# DriverBoard.net
KiCad netlist of a schematic drawn in Altium Designer
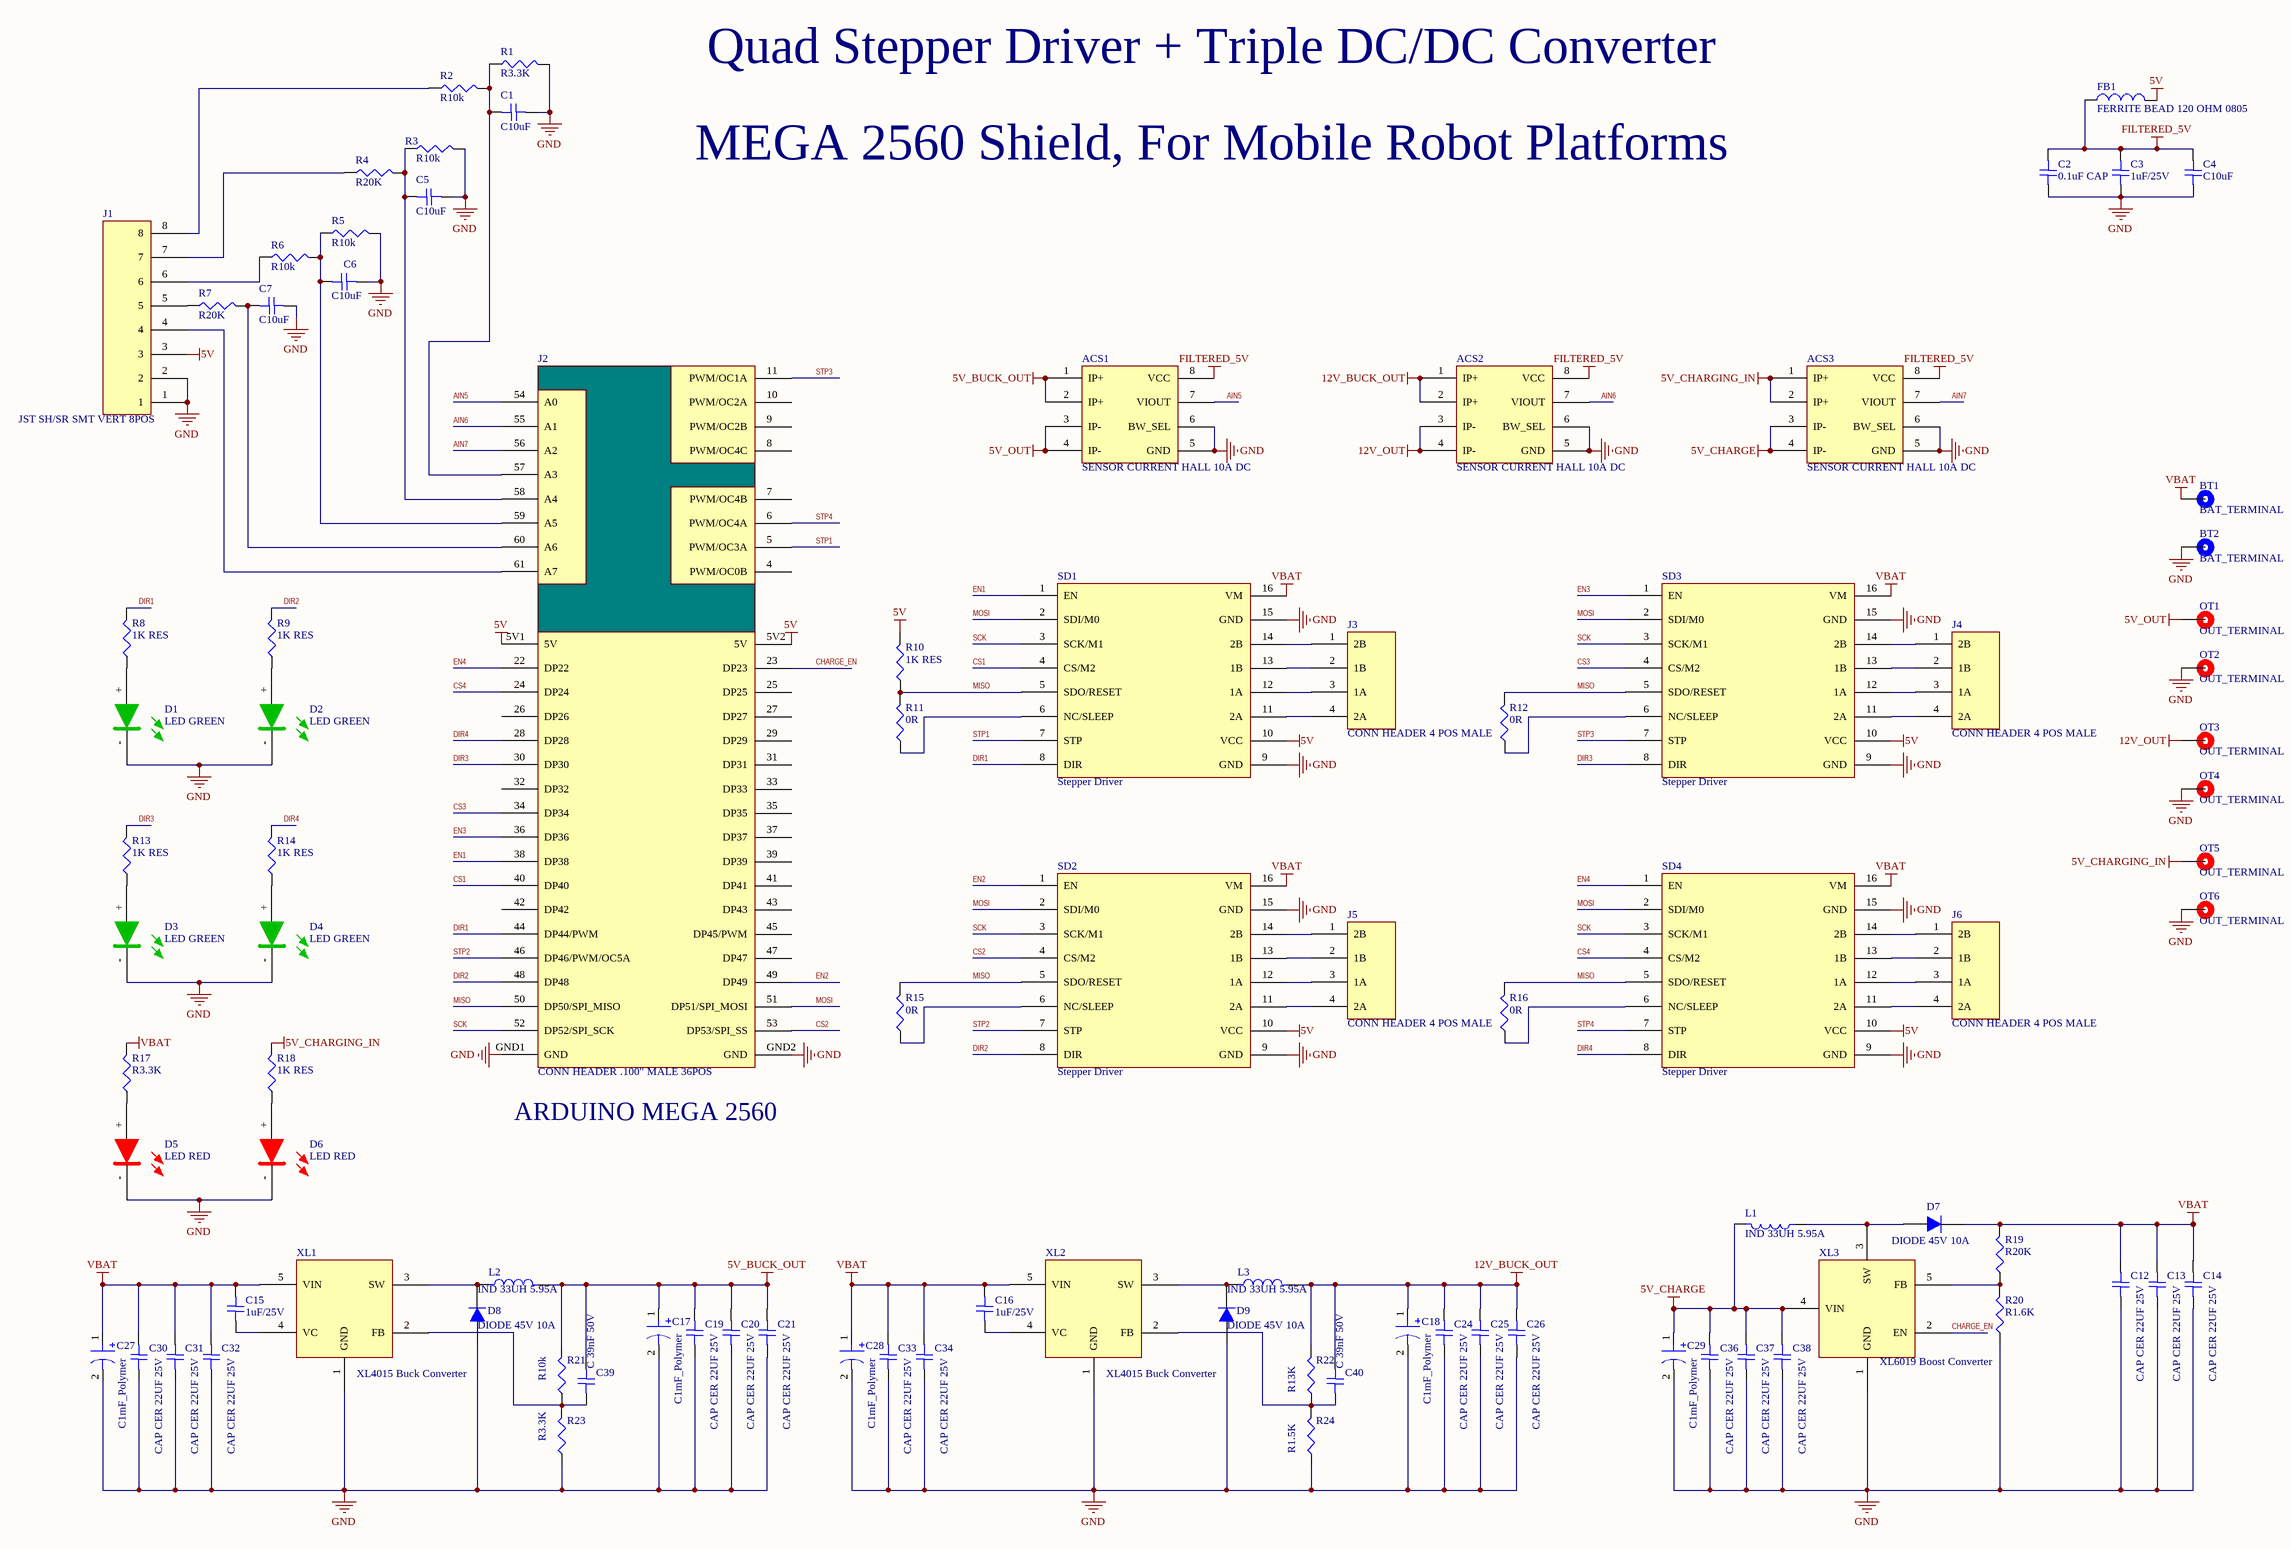
[diagram p0: DriverBoard.SchDoc]

(export (version "E")
  (design (tool "Eeschema 10.0.6"))
  (components
    (comp (ref "ACS1")
      (value "SENSOR CURRENT HALL 10A DC")
      (footprint "SOIC_8")
      (fields
        (field (name "MANUFACTURER") "Allegro MicroSystems")
        (field (name "MANUFACTURER PART NUMBER") "ACS723LLCTR-10AU-T")
      )
      (libsource (lib "DriverBoard") (part "ACS723LLCTR-10AU-T"))
    )
    (comp (ref "ACS2")
      (value "SENSOR CURRENT HALL 10A DC")
      (footprint "SOIC_8")
      (fields
        (field (name "MANUFACTURER") "Allegro MicroSystems")
        (field (name "MANUFACTURER PART NUMBER") "ACS723LLCTR-10AU-T")
      )
      (libsource (lib "DriverBoard") (part "ACS723LLCTR-10AU-T"))
    )
    (comp (ref "ACS3")
      (value "SENSOR CURRENT HALL 10A DC")
      (footprint "SOIC_8")
      (fields
        (field (name "MANUFACTURER") "Allegro MicroSystems")
        (field (name "MANUFACTURER PART NUMBER") "ACS723LLCTR-10AU-T")
      )
      (libsource (lib "DriverBoard") (part "ACS723LLCTR-10AU-T"))
    )
    (comp (ref "BT1")
      (value "BAT_TERMINAL")
      (footprint "BATTERY_TERMINALS")
      (libsource (lib "DriverBoard") (part "BAT_TERMINAL"))
    )
    (comp (ref "BT2")
      (value "BAT_TERMINAL")
      (footprint "BATTERY_TERMINALS")
      (libsource (lib "DriverBoard") (part "BAT_TERMINAL"))
    )
    (comp (ref "C1")
      (value "C10uF")
      (footprint "C0805")
      (description "Cap Ceramic 10uF 10V X5R 10% SMD 0805 85C Embossed T/R")
      (fields
        (field (name "MANUFACTURER") "Samsung")
        (field (name "MANUFACTURER PART NUMBER") "CL21A106KPFNNNG")
      )
      (libsource (lib "DriverBoard") (part "CL21A106KPFNNNG"))
    )
    (comp (ref "C2")
      (value "0.1uF CAP")
      (footprint "C0805")
      (description "Cap Ceramic 0.1uF 50V Y5V -20% to 80% SMD 0805 85C Paper T/R")
      (fields
        (field (name "MANUFACTURER") "Samsung")
        (field (name "MANUFACTURER PART NUMBER") "CL21F104ZBCNNNC")
      )
      (libsource (lib "DriverBoard") (part "CL21F104ZBCNNNC"))
    )
    (comp (ref "C3")
      (value "1uF/25V")
      (footprint "C0805")
      (description "CAP CER 1UF 25V X5R 0805")
      (fields
        (field (name "MANUFACTURER") "TDK Corporation")
        (field (name "MANUFACTURER PART NUMBER") "C2012X5R1E105K125AA")
      )
      (libsource (lib "DriverBoard") (part "C2012X5R1E105K125AA"))
    )
    (comp (ref "C4")
      (value "C10uF")
      (footprint "C0805")
      (description "Cap Ceramic 10uF 10V X5R 10% SMD 0805 85C Embossed T/R")
      (fields
        (field (name "MANUFACTURER") "Samsung")
        (field (name "MANUFACTURER PART NUMBER") "CL21A106KPFNNNG")
      )
      (libsource (lib "DriverBoard") (part "CL21A106KPFNNNG"))
    )
    (comp (ref "C5")
      (value "C10uF")
      (footprint "C0805")
      (description "Cap Ceramic 10uF 10V X5R 10% SMD 0805 85C Embossed T/R")
      (fields
        (field (name "MANUFACTURER") "Samsung")
        (field (name "MANUFACTURER PART NUMBER") "CL21A106KPFNNNG")
      )
      (libsource (lib "DriverBoard") (part "CL21A106KPFNNNG"))
    )
    (comp (ref "C6")
      (value "C10uF")
      (footprint "C0805")
      (description "Cap Ceramic 10uF 10V X5R 10% SMD 0805 85C Embossed T/R")
      (fields
        (field (name "MANUFACTURER") "Samsung")
        (field (name "MANUFACTURER PART NUMBER") "CL21A106KPFNNNG")
      )
      (libsource (lib "DriverBoard") (part "CL21A106KPFNNNG"))
    )
    (comp (ref "C7")
      (value "C10uF")
      (footprint "C0805")
      (description "Cap Ceramic 10uF 10V X5R 10% SMD 0805 85C Embossed T/R")
      (fields
        (field (name "MANUFACTURER") "Samsung")
        (field (name "MANUFACTURER PART NUMBER") "CL21A106KPFNNNG")
      )
      (libsource (lib "DriverBoard") (part "CL21A106KPFNNNG"))
    )
    (comp (ref "C12")
      (value "CAP CER 22UF 25V")
      (footprint "C1210")
      (description "CAP CER 22UF 25V X5R 1210")
      (fields
        (field (name "MANUFACTURER") "Samsung")
        (field (name "MANUFACTURER PART NUMBER") "CL32A226MAJNNNE")
      )
      (libsource (lib "DriverBoard") (part "CL32A226MAJNNNE"))
    )
    (comp (ref "C13")
      (value "CAP CER 22UF 25V")
      (footprint "C1210")
      (description "CAP CER 22UF 25V X5R 1210")
      (fields
        (field (name "MANUFACTURER") "Samsung")
        (field (name "MANUFACTURER PART NUMBER") "CL32A226MAJNNNE")
      )
      (libsource (lib "DriverBoard") (part "CL32A226MAJNNNE"))
    )
    (comp (ref "C14")
      (value "CAP CER 22UF 25V")
      (footprint "C1210")
      (description "CAP CER 22UF 25V X5R 1210")
      (fields
        (field (name "MANUFACTURER") "Samsung")
        (field (name "MANUFACTURER PART NUMBER") "CL32A226MAJNNNE")
      )
      (libsource (lib "DriverBoard") (part "CL32A226MAJNNNE"))
    )
    (comp (ref "C15")
      (value "1uF/25V")
      (footprint "C0805")
      (description "CAP CER 1UF 25V X5R 0805")
      (fields
        (field (name "MANUFACTURER") "TDK Corporation")
        (field (name "MANUFACTURER PART NUMBER") "C2012X5R1E105K125AA")
      )
      (libsource (lib "DriverBoard") (part "C2012X5R1E105K125AA"))
    )
    (comp (ref "C16")
      (value "1uF/25V")
      (footprint "C0805")
      (description "CAP CER 1UF 25V X5R 0805")
      (fields
        (field (name "MANUFACTURER") "TDK Corporation")
        (field (name "MANUFACTURER PART NUMBER") "C2012X5R1E105K125AA")
      )
      (libsource (lib "DriverBoard") (part "C2012X5R1E105K125AA"))
    )
    (comp (ref "C17")
      (value "C1mF_Polymer")
      (footprint "POLY_CAP_10X21")
      (description "Cap Aluminum Polymer 680uF 20VDC 20% (10 X 11.5mm) Radial 5mm 0.012 Ohm 5400mA 2000h 105C Bulk")
      (fields
        (field (name "MANUFACTURER") "United Chemi-Con")
        (field (name "MANUFACTURER PART NUMBER") "APSG200ELL681MJB5S")
      )
      (libsource (lib "DriverBoard") (part "APSG200ELL681MJB5S"))
    )
    (comp (ref "C18")
      (value "C1mF_Polymer")
      (footprint "POLY_CAP_10X21")
      (description "Cap Aluminum Polymer 680uF 20VDC 20% (10 X 11.5mm) Radial 5mm 0.012 Ohm 5400mA 2000h 105C Bulk")
      (fields
        (field (name "MANUFACTURER") "United Chemi-Con")
        (field (name "MANUFACTURER PART NUMBER") "APSG200ELL681MJB5S")
      )
      (libsource (lib "DriverBoard") (part "APSG200ELL681MJB5S"))
    )
    (comp (ref "C19")
      (value "CAP CER 22UF 25V")
      (footprint "C1210")
      (description "CAP CER 22UF 25V X5R 1210")
      (fields
        (field (name "MANUFACTURER") "Samsung")
        (field (name "MANUFACTURER PART NUMBER") "CL32A226MAJNNNE")
      )
      (libsource (lib "DriverBoard") (part "CL32A226MAJNNNE"))
    )
    (comp (ref "C20")
      (value "CAP CER 22UF 25V")
      (footprint "C1210")
      (description "CAP CER 22UF 25V X5R 1210")
      (fields
        (field (name "MANUFACTURER") "Samsung")
        (field (name "MANUFACTURER PART NUMBER") "CL32A226MAJNNNE")
      )
      (libsource (lib "DriverBoard") (part "CL32A226MAJNNNE"))
    )
    (comp (ref "C21")
      (value "CAP CER 22UF 25V")
      (footprint "C1210")
      (description "CAP CER 22UF 25V X5R 1210")
      (fields
        (field (name "MANUFACTURER") "Samsung")
        (field (name "MANUFACTURER PART NUMBER") "CL32A226MAJNNNE")
      )
      (libsource (lib "DriverBoard") (part "CL32A226MAJNNNE"))
    )
    (comp (ref "C24")
      (value "CAP CER 22UF 25V")
      (footprint "C1210")
      (description "CAP CER 22UF 25V X5R 1210")
      (fields
        (field (name "MANUFACTURER") "Samsung")
        (field (name "MANUFACTURER PART NUMBER") "CL32A226MAJNNNE")
      )
      (libsource (lib "DriverBoard") (part "CL32A226MAJNNNE"))
    )
    (comp (ref "C25")
      (value "CAP CER 22UF 25V")
      (footprint "C1210")
      (description "CAP CER 22UF 25V X5R 1210")
      (fields
        (field (name "MANUFACTURER") "Samsung")
        (field (name "MANUFACTURER PART NUMBER") "CL32A226MAJNNNE")
      )
      (libsource (lib "DriverBoard") (part "CL32A226MAJNNNE"))
    )
    (comp (ref "C26")
      (value "CAP CER 22UF 25V")
      (footprint "C1210")
      (description "CAP CER 22UF 25V X5R 1210")
      (fields
        (field (name "MANUFACTURER") "Samsung")
        (field (name "MANUFACTURER PART NUMBER") "CL32A226MAJNNNE")
      )
      (libsource (lib "DriverBoard") (part "CL32A226MAJNNNE"))
    )
    (comp (ref "C27")
      (value "C1mF_Polymer")
      (footprint "POLY_CAP_10X21")
      (description "Cap Aluminum Polymer 680uF 20VDC 20% (10 X 11.5mm) Radial 5mm 0.012 Ohm 5400mA 2000h 105C Bulk")
      (fields
        (field (name "MANUFACTURER") "United Chemi-Con")
        (field (name "MANUFACTURER PART NUMBER") "APSG200ELL681MJB5S")
      )
      (libsource (lib "DriverBoard") (part "APSG200ELL681MJB5S"))
    )
    (comp (ref "C28")
      (value "C1mF_Polymer")
      (footprint "POLY_CAP_10X21")
      (description "Cap Aluminum Polymer 680uF 20VDC 20% (10 X 11.5mm) Radial 5mm 0.012 Ohm 5400mA 2000h 105C Bulk")
      (fields
        (field (name "MANUFACTURER") "United Chemi-Con")
        (field (name "MANUFACTURER PART NUMBER") "APSG200ELL681MJB5S")
      )
      (libsource (lib "DriverBoard") (part "APSG200ELL681MJB5S"))
    )
    (comp (ref "C29")
      (value "C1mF_Polymer")
      (footprint "POLY_CAP_10X21")
      (description "Cap Aluminum Polymer 680uF 20VDC 20% (10 X 11.5mm) Radial 5mm 0.012 Ohm 5400mA 2000h 105C Bulk")
      (fields
        (field (name "MANUFACTURER") "United Chemi-Con")
        (field (name "MANUFACTURER PART NUMBER") "APSG200ELL681MJB5S")
      )
      (libsource (lib "DriverBoard") (part "APSG200ELL681MJB5S"))
    )
    (comp (ref "C30")
      (value "CAP CER 22UF 25V")
      (footprint "C1210")
      (description "CAP CER 22UF 25V X5R 1210")
      (fields
        (field (name "MANUFACTURER") "Samsung")
        (field (name "MANUFACTURER PART NUMBER") "CL32A226MAJNNNE")
      )
      (libsource (lib "DriverBoard") (part "CL32A226MAJNNNE"))
    )
    (comp (ref "C31")
      (value "CAP CER 22UF 25V")
      (footprint "C1210")
      (description "CAP CER 22UF 25V X5R 1210")
      (fields
        (field (name "MANUFACTURER") "Samsung")
        (field (name "MANUFACTURER PART NUMBER") "CL32A226MAJNNNE")
      )
      (libsource (lib "DriverBoard") (part "CL32A226MAJNNNE"))
    )
    (comp (ref "C32")
      (value "CAP CER 22UF 25V")
      (footprint "C1210")
      (description "CAP CER 22UF 25V X5R 1210")
      (fields
        (field (name "MANUFACTURER") "Samsung")
        (field (name "MANUFACTURER PART NUMBER") "CL32A226MAJNNNE")
      )
      (libsource (lib "DriverBoard") (part "CL32A226MAJNNNE"))
    )
    (comp (ref "C33")
      (value "CAP CER 22UF 25V")
      (footprint "C1210")
      (description "CAP CER 22UF 25V X5R 1210")
      (fields
        (field (name "MANUFACTURER") "Samsung")
        (field (name "MANUFACTURER PART NUMBER") "CL32A226MAJNNNE")
      )
      (libsource (lib "DriverBoard") (part "CL32A226MAJNNNE"))
    )
    (comp (ref "C34")
      (value "CAP CER 22UF 25V")
      (footprint "C1210")
      (description "CAP CER 22UF 25V X5R 1210")
      (fields
        (field (name "MANUFACTURER") "Samsung")
        (field (name "MANUFACTURER PART NUMBER") "CL32A226MAJNNNE")
      )
      (libsource (lib "DriverBoard") (part "CL32A226MAJNNNE"))
    )
    (comp (ref "C36")
      (value "CAP CER 22UF 25V")
      (footprint "C1210")
      (description "CAP CER 22UF 25V X5R 1210")
      (fields
        (field (name "MANUFACTURER") "Samsung")
        (field (name "MANUFACTURER PART NUMBER") "CL32A226MAJNNNE")
      )
      (libsource (lib "DriverBoard") (part "CL32A226MAJNNNE"))
    )
    (comp (ref "C37")
      (value "CAP CER 22UF 25V")
      (footprint "C1210")
      (description "CAP CER 22UF 25V X5R 1210")
      (fields
        (field (name "MANUFACTURER") "Samsung")
        (field (name "MANUFACTURER PART NUMBER") "CL32A226MAJNNNE")
      )
      (libsource (lib "DriverBoard") (part "CL32A226MAJNNNE"))
    )
    (comp (ref "C38")
      (value "CAP CER 22UF 25V")
      (footprint "C1210")
      (description "CAP CER 22UF 25V X5R 1210")
      (fields
        (field (name "MANUFACTURER") "Samsung")
        (field (name "MANUFACTURER PART NUMBER") "CL32A226MAJNNNE")
      )
      (libsource (lib "DriverBoard") (part "CL32A226MAJNNNE"))
    )
    (comp (ref "C39")
      (value "C 39nF 50V")
      (footprint "C0805")
      (description "Multilayer Ceramic Capacitors 50volts 39000pF X7R 10%")
      (fields
        (field (name "MANUFACTURER") "KEMET")
        (field (name "MANUFACTURER PART NUMBER") "C0805C393K5RACTU")
      )
      (libsource (lib "DriverBoard") (part "C0805C393K5RACTU"))
    )
    (comp (ref "C40")
      (value "C 39nF 50V")
      (footprint "C0805")
      (description "Multilayer Ceramic Capacitors 50volts 39000pF X7R 10%")
      (fields
        (field (name "MANUFACTURER") "KEMET")
        (field (name "MANUFACTURER PART NUMBER") "C0805C393K5RACTU")
      )
      (libsource (lib "DriverBoard") (part "C0805C393K5RACTU"))
    )
    (comp (ref "D1")
      (value "LED GREEN")
      (footprint "LED_0805")
      (description "LED GREEN CLEAR CHIP SMD")
      (fields
        (field (name "MANUFACTURER") "Vishay Lite-On")
        (field (name "MANUFACTURER PART NUMBER") "LTST-C171GKT")
      )
      (libsource (lib "DriverBoard") (part "LTST-C171GKT"))
    )
    (comp (ref "D2")
      (value "LED GREEN")
      (footprint "LED_0805")
      (description "LED GREEN CLEAR CHIP SMD")
      (fields
        (field (name "MANUFACTURER") "Vishay Lite-On")
        (field (name "MANUFACTURER PART NUMBER") "LTST-C171GKT")
      )
      (libsource (lib "DriverBoard") (part "LTST-C171GKT"))
    )
    (comp (ref "D3")
      (value "LED GREEN")
      (footprint "LED_0805")
      (description "LED GREEN CLEAR CHIP SMD")
      (fields
        (field (name "MANUFACTURER") "Vishay Lite-On")
        (field (name "MANUFACTURER PART NUMBER") "LTST-C171GKT")
      )
      (libsource (lib "DriverBoard") (part "LTST-C171GKT"))
    )
    (comp (ref "D4")
      (value "LED GREEN")
      (footprint "LED_0805")
      (description "LED GREEN CLEAR CHIP SMD")
      (fields
        (field (name "MANUFACTURER") "Vishay Lite-On")
        (field (name "MANUFACTURER PART NUMBER") "LTST-C171GKT")
      )
      (libsource (lib "DriverBoard") (part "LTST-C171GKT"))
    )
    (comp (ref "D5")
      (value "LED RED")
      (footprint "LED_0805")
      (description "LED RED CLEAR SMD")
      (fields
        (field (name "MANUFACTURER") "Vishay Lite-On")
        (field (name "MANUFACTURER PART NUMBER") "LTST-C171KRKT")
      )
      (libsource (lib "DriverBoard") (part "LTST-C171KRKT"))
    )
    (comp (ref "D6")
      (value "LED RED")
      (footprint "LED_0805")
      (description "LED RED CLEAR SMD")
      (fields
        (field (name "MANUFACTURER") "Vishay Lite-On")
        (field (name "MANUFACTURER PART NUMBER") "LTST-C171KRKT")
      )
      (libsource (lib "DriverBoard") (part "LTST-C171KRKT"))
    )
    (comp (ref "D7")
      (value "DIODE 45V 10A")
      (footprint "TO252_3")
      (description "DIODE SCHOTTKY 45V 10A DPAK")
      (fields
        (field (name "MANUFACTURER") "ON Semiconductor")
        (field (name "MANUFACTURER PART NUMBER") "MBRD1045T4G")
      )
      (libsource (lib "DriverBoard") (part "MBRD1045T4G"))
    )
    (comp (ref "D8")
      (value "DIODE 45V 10A")
      (footprint "TO252_3")
      (description "DIODE SCHOTTKY 45V 10A DPAK")
      (fields
        (field (name "MANUFACTURER") "ON Semiconductor")
        (field (name "MANUFACTURER PART NUMBER") "MBRD1045T4G")
      )
      (libsource (lib "DriverBoard") (part "MBRD1045T4G"))
    )
    (comp (ref "D9")
      (value "DIODE 45V 10A")
      (footprint "TO252_3")
      (description "DIODE SCHOTTKY 45V 10A DPAK")
      (fields
        (field (name "MANUFACTURER") "ON Semiconductor")
        (field (name "MANUFACTURER PART NUMBER") "MBRD1045T4G")
      )
      (libsource (lib "DriverBoard") (part "MBRD1045T4G"))
    )
    (comp (ref "FB1")
      (value "FERRITE BEAD 120 OHM 0805")
      (footprint "FB_0805")
      (description "FERRITE BEAD 120 OHM 0805 1LN")
      (fields
        (field (name "MANUFACTURER") "Wurth Electronics")
        (field (name "MANUFACTURER PART NUMBER") "742792023")
      )
      (libsource (lib "DriverBoard") (part "742792023"))
    )
    (comp (ref "J1")
      (value "JST SH/SR SMT VERT 8POS")
      (footprint "JST_SH_8")
      (description "CONN RCPT SR 8 POS 1.0MM TIN")
      (fields (field (name "MANUFACTURER") "JST") (field (name "MANUFACTURER PART NUMBER") "08SR-3S"))
      (libsource (lib "DriverBoard") (part "08SR-3S"))
    )
    (comp (ref "J2")
      (value "CONN HEADER .100\" MALE 36POS")
      (footprint "DIP36_MALE")
      (description "CONN HEADER .100\" DUAL STR 36POS")
      (fields
        (field (name "MANUFACTURER") "Sullins")
        (field (name "MANUFACTURER PART NUMBER") "PREC018DAAN-RC")
      )
      (libsource (lib "DriverBoard") (part "PREC018DAAN-RC"))
    )
    (comp (ref "J3")
      (value "CONN HEADER 4 POS MALE")
      (footprint "DIP4")
      (description "CONN HEADER VERT 4POS 2.54MM")
      (fields
        (field (name "MANUFACTURER") "Sullins")
        (field (name "MANUFACTURER PART NUMBER") "PREC004SAAN-RC")
      )
      (libsource (lib "DriverBoard") (part "PREC004SAAN-RC"))
    )
    (comp (ref "J4")
      (value "CONN HEADER 4 POS MALE")
      (footprint "DIP4")
      (description "CONN HEADER VERT 4POS 2.54MM")
      (fields
        (field (name "MANUFACTURER") "Sullins")
        (field (name "MANUFACTURER PART NUMBER") "PREC004SAAN-RC")
      )
      (libsource (lib "DriverBoard") (part "PREC004SAAN-RC"))
    )
    (comp (ref "J5")
      (value "CONN HEADER 4 POS MALE")
      (footprint "DIP4")
      (description "CONN HEADER VERT 4POS 2.54MM")
      (fields
        (field (name "MANUFACTURER") "Sullins")
        (field (name "MANUFACTURER PART NUMBER") "PREC004SAAN-RC")
      )
      (libsource (lib "DriverBoard") (part "PREC004SAAN-RC"))
    )
    (comp (ref "J6")
      (value "CONN HEADER 4 POS MALE")
      (footprint "DIP4")
      (description "CONN HEADER VERT 4POS 2.54MM")
      (fields
        (field (name "MANUFACTURER") "Sullins")
        (field (name "MANUFACTURER PART NUMBER") "PREC004SAAN-RC")
      )
      (libsource (lib "DriverBoard") (part "PREC004SAAN-RC"))
    )
    (comp (ref "L1")
      (value "IND 33UH 5.95A")
      (footprint "13X13X9IND")
      (description "COILCRAFT   SER1390-333MLD   INDUCTOR, 33UH, 5.95A, 20%, 15.7MHZ,REEL")
      (fields
        (field (name "MANUFACTURER") "Coilcraft")
        (field (name "MANUFACTURER PART NUMBER") "SER1390-333MLD")
      )
      (libsource (lib "DriverBoard") (part "SER1390-333MLD"))
    )
    (comp (ref "L2")
      (value "IND 33UH 5.95A")
      (footprint "13X13X9IND")
      (description "COILCRAFT   SER1390-333MLD   INDUCTOR, 33UH, 5.95A, 20%, 15.7MHZ,REEL")
      (fields
        (field (name "MANUFACTURER") "Coilcraft")
        (field (name "MANUFACTURER PART NUMBER") "SER1390-333MLD")
      )
      (libsource (lib "DriverBoard") (part "SER1390-333MLD"))
    )
    (comp (ref "L3")
      (value "IND 33UH 5.95A")
      (footprint "13X13X9IND")
      (description "COILCRAFT   SER1390-333MLD   INDUCTOR, 33UH, 5.95A, 20%, 15.7MHZ,REEL")
      (fields
        (field (name "MANUFACTURER") "Coilcraft")
        (field (name "MANUFACTURER PART NUMBER") "SER1390-333MLD")
      )
      (libsource (lib "DriverBoard") (part "SER1390-333MLD"))
    )
    (comp (ref "OT1")
      (value "OUT_TERMINAL")
      (footprint "OUTPUT_TERMINALS")
      (libsource (lib "DriverBoard") (part "OUT_TERMINAL"))
    )
    (comp (ref "OT2")
      (value "OUT_TERMINAL")
      (footprint "OUTPUT_TERMINALS")
      (libsource (lib "DriverBoard") (part "OUT_TERMINAL"))
    )
    (comp (ref "OT3")
      (value "OUT_TERMINAL")
      (footprint "OUTPUT_TERMINALS")
      (libsource (lib "DriverBoard") (part "OUT_TERMINAL"))
    )
    (comp (ref "OT4")
      (value "OUT_TERMINAL")
      (footprint "OUTPUT_TERMINALS")
      (libsource (lib "DriverBoard") (part "OUT_TERMINAL"))
    )
    (comp (ref "OT5")
      (value "OUT_TERMINAL")
      (footprint "OUTPUT_TERMINALS")
      (libsource (lib "DriverBoard") (part "OUT_TERMINAL"))
    )
    (comp (ref "OT6")
      (value "OUT_TERMINAL")
      (footprint "OUTPUT_TERMINALS")
      (libsource (lib "DriverBoard") (part "OUT_TERMINAL"))
    )
    (comp (ref "R1")
      (value "R3.3K")
      (footprint "R0805")
      (description "RES SMD 3.3K OHM 1% 1/8W 0805")
      (fields
        (field (name "MANUFACTURER") "Yageo")
        (field (name "MANUFACTURER PART NUMBER") "RC0805FR-073K3L")
      )
      (libsource (lib "DriverBoard") (part "RC0805FR-073K3L"))
    )
    (comp (ref "R2")
      (value "R10k")
      (footprint "R0805")
      (description "RES SMD 10K OHM 1% 1/8W 0805")
      (fields
        (field (name "MANUFACTURER") "Yageo")
        (field (name "MANUFACTURER PART NUMBER") "RC0805FR-0710KL")
      )
      (libsource (lib "DriverBoard") (part "RC0805FR-0710KL"))
    )
    (comp (ref "R3")
      (value "R10k")
      (footprint "R0805")
      (description "RES SMD 10K OHM 1% 1/8W 0805")
      (fields
        (field (name "MANUFACTURER") "Yageo")
        (field (name "MANUFACTURER PART NUMBER") "RC0805FR-0710KL")
      )
      (libsource (lib "DriverBoard") (part "RC0805FR-0710KL"))
    )
    (comp (ref "R4")
      (value "R20K")
      (footprint "R0805")
      (description "RES SMD 20K OHM 0.1% 1/8W 0805")
      (fields
        (field (name "MANUFACTURER") "Yageo")
        (field (name "MANUFACTURER PART NUMBER") "RT0805BRC0720KL")
      )
      (libsource (lib "DriverBoard") (part "RT0805BRC0720KL"))
    )
    (comp (ref "R5")
      (value "R10k")
      (footprint "R0805")
      (description "RES SMD 10K OHM 1% 1/8W 0805")
      (fields
        (field (name "MANUFACTURER") "Yageo")
        (field (name "MANUFACTURER PART NUMBER") "RC0805FR-0710KL")
      )
      (libsource (lib "DriverBoard") (part "RC0805FR-0710KL"))
    )
    (comp (ref "R6")
      (value "R10k")
      (footprint "R0805")
      (description "RES SMD 10K OHM 1% 1/8W 0805")
      (fields
        (field (name "MANUFACTURER") "Yageo")
        (field (name "MANUFACTURER PART NUMBER") "RC0805FR-0710KL")
      )
      (libsource (lib "DriverBoard") (part "RC0805FR-0710KL"))
    )
    (comp (ref "R7")
      (value "R20K")
      (footprint "R0805")
      (description "RES SMD 20K OHM 0.1% 1/8W 0805")
      (fields
        (field (name "MANUFACTURER") "Yageo")
        (field (name "MANUFACTURER PART NUMBER") "RT0805BRC0720KL")
      )
      (libsource (lib "DriverBoard") (part "RT0805BRC0720KL"))
    )
    (comp (ref "R8")
      (value "1K RES")
      (footprint "R0805")
      (description "RES 1K OHM 1% 1/4W 0805")
      (fields
        (field (name "MANUFACTURER") "Stackpole Electronics")
        (field (name "MANUFACTURER PART NUMBER") "RNCP0805FTD1K00")
      )
      (libsource (lib "DriverBoard") (part "RNCP0805FTD1K00"))
    )
    (comp (ref "R9")
      (value "1K RES")
      (footprint "R0805")
      (description "RES 1K OHM 1% 1/4W 0805")
      (fields
        (field (name "MANUFACTURER") "Stackpole Electronics")
        (field (name "MANUFACTURER PART NUMBER") "RNCP0805FTD1K00")
      )
      (libsource (lib "DriverBoard") (part "RNCP0805FTD1K00"))
    )
    (comp (ref "R10")
      (value "1K RES")
      (footprint "R0805")
      (description "RES 1K OHM 1% 1/4W 0805")
      (fields
        (field (name "MANUFACTURER") "Stackpole Electronics")
        (field (name "MANUFACTURER PART NUMBER") "RNCP0805FTD1K00")
      )
      (libsource (lib "DriverBoard") (part "RNCP0805FTD1K00"))
    )
    (comp (ref "R11")
      (value "0R")
      (footprint "R0805")
      (description "RES SMD 0 OHM JUMPER 1/8W 0805")
      (fields
        (field (name "MANUFACTURER") "Yageo")
        (field (name "MANUFACTURER PART NUMBER") "RC0805JR-070RL")
      )
      (libsource (lib "DriverBoard") (part "RC0805JR-070RL"))
    )
    (comp (ref "R12")
      (value "0R")
      (footprint "R0805")
      (description "RES SMD 0 OHM JUMPER 1/8W 0805")
      (fields
        (field (name "MANUFACTURER") "Yageo")
        (field (name "MANUFACTURER PART NUMBER") "RC0805JR-070RL")
      )
      (libsource (lib "DriverBoard") (part "RC0805JR-070RL"))
    )
    (comp (ref "R13")
      (value "1K RES")
      (footprint "R0805")
      (description "RES 1K OHM 1% 1/4W 0805")
      (fields
        (field (name "MANUFACTURER") "Stackpole Electronics")
        (field (name "MANUFACTURER PART NUMBER") "RNCP0805FTD1K00")
      )
      (libsource (lib "DriverBoard") (part "RNCP0805FTD1K00"))
    )
    (comp (ref "R14")
      (value "1K RES")
      (footprint "R0805")
      (description "RES 1K OHM 1% 1/4W 0805")
      (fields
        (field (name "MANUFACTURER") "Stackpole Electronics")
        (field (name "MANUFACTURER PART NUMBER") "RNCP0805FTD1K00")
      )
      (libsource (lib "DriverBoard") (part "RNCP0805FTD1K00"))
    )
    (comp (ref "R15")
      (value "0R")
      (footprint "R0805")
      (description "RES SMD 0 OHM JUMPER 1/8W 0805")
      (fields
        (field (name "MANUFACTURER") "Yageo")
        (field (name "MANUFACTURER PART NUMBER") "RC0805JR-070RL")
      )
      (libsource (lib "DriverBoard") (part "RC0805JR-070RL"))
    )
    (comp (ref "R16")
      (value "0R")
      (footprint "R0805")
      (description "RES SMD 0 OHM JUMPER 1/8W 0805")
      (fields
        (field (name "MANUFACTURER") "Yageo")
        (field (name "MANUFACTURER PART NUMBER") "RC0805JR-070RL")
      )
      (libsource (lib "DriverBoard") (part "RC0805JR-070RL"))
    )
    (comp (ref "R17")
      (value "R3.3K")
      (footprint "R0805")
      (description "RES SMD 3.3K OHM 1% 1/8W 0805")
      (fields
        (field (name "MANUFACTURER") "Yageo")
        (field (name "MANUFACTURER PART NUMBER") "RC0805FR-073K3L")
      )
      (libsource (lib "DriverBoard") (part "RC0805FR-073K3L"))
    )
    (comp (ref "R18")
      (value "1K RES")
      (footprint "R0805")
      (description "RES 1K OHM 1% 1/4W 0805")
      (fields
        (field (name "MANUFACTURER") "Stackpole Electronics")
        (field (name "MANUFACTURER PART NUMBER") "RNCP0805FTD1K00")
      )
      (libsource (lib "DriverBoard") (part "RNCP0805FTD1K00"))
    )
    (comp (ref "R19")
      (value "R20K")
      (footprint "R0805")
      (description "RES SMD 20K OHM 0.1% 1/8W 0805")
      (fields
        (field (name "MANUFACTURER") "Yageo")
        (field (name "MANUFACTURER PART NUMBER") "RT0805BRC0720KL")
      )
      (libsource (lib "DriverBoard") (part "RT0805BRC0720KL"))
    )
    (comp (ref "R20")
      (value "R1.6K")
      (footprint "R0805")
      (description "RES SMD 1.6K OHM 1% 1/8W 0805")
      (fields
        (field (name "MANUFACTURER") "Yageo")
        (field (name "MANUFACTURER PART NUMBER") "RC0805FR-071K6L")
      )
      (libsource (lib "DriverBoard") (part "RC0805FR-071K6L"))
    )
    (comp (ref "R21")
      (value "R10k")
      (footprint "R0805")
      (description "RES SMD 10K OHM 1% 1/8W 0805")
      (fields
        (field (name "MANUFACTURER") "Yageo")
        (field (name "MANUFACTURER PART NUMBER") "RC0805FR-0710KL")
      )
      (libsource (lib "DriverBoard") (part "RC0805FR-0710KL"))
    )
    (comp (ref "R22")
      (value "R13K")
      (footprint "R0805")
      (description "RES SMD 13K OHM 1% 1/8W 0805")
      (fields
        (field (name "MANUFACTURER") "Yageo")
        (field (name "MANUFACTURER PART NUMBER") "RC0805FR-0713KL")
      )
      (libsource (lib "DriverBoard") (part "RC0805FR-0713KL"))
    )
    (comp (ref "R23")
      (value "R3.3K")
      (footprint "R0805")
      (description "RES SMD 3.3K OHM 1% 1/8W 0805")
      (fields
        (field (name "MANUFACTURER") "Yageo")
        (field (name "MANUFACTURER PART NUMBER") "RC0805FR-073K3L")
      )
      (libsource (lib "DriverBoard") (part "RC0805FR-073K3L"))
    )
    (comp (ref "R24")
      (value "R1.5K")
      (footprint "R0805")
      (description "RES SMD 1.5K OHM 1% 1/8W 0805")
      (fields
        (field (name "MANUFACTURER") "Yageo")
        (field (name "MANUFACTURER PART NUMBER") "RC0805FR-071K5L")
      )
      (libsource (lib "DriverBoard") (part "RC0805FR-071K5L"))
    )
    (comp (ref "SD1")
      (value "Stepper Driver")
      (footprint "DIP16_Stepper")
      (description "TMC2130, DRV8825, TB67S109, A4988")
      (libsource (lib "DriverBoard") (part "SilentStepStick_BigTreeTech_TMC2130V1.1"))
    )
    (comp (ref "SD2")
      (value "Stepper Driver")
      (footprint "DIP16_Stepper")
      (description "TMC2130, DRV8825, TB67S109, A4988")
      (libsource (lib "DriverBoard") (part "SilentStepStick_BigTreeTech_TMC2130V1.1"))
    )
    (comp (ref "SD3")
      (value "Stepper Driver")
      (footprint "DIP16_Stepper")
      (description "TMC2130, DRV8825, TB67S109, A4988")
      (libsource (lib "DriverBoard") (part "SilentStepStick_BigTreeTech_TMC2130V1.1"))
    )
    (comp (ref "SD4")
      (value "Stepper Driver")
      (footprint "DIP16_Stepper")
      (description "TMC2130, DRV8825, TB67S109, A4988")
      (libsource (lib "DriverBoard") (part "SilentStepStick_BigTreeTech_TMC2130V1.1"))
    )
    (comp (ref "XL1")
      (value "XL4015 Buck Converter")
      (footprint "TO263-5L")
      (description "XL Semi Buck Converter, not available in USA")
      (libsource (lib "DriverBoard") (part "XL4015"))
    )
    (comp (ref "XL2")
      (value "XL4015 Buck Converter")
      (footprint "TO263-5L")
      (description "XL Semi Buck Converter, not available in USA")
      (libsource (lib "DriverBoard") (part "XL4015"))
    )
    (comp (ref "XL3")
      (value "XL6019 Boost Converter")
      (footprint "TO263-5L")
      (description "XL Semi Boost Converter, not available in USA")
      (libsource (lib "DriverBoard") (part "XL6019"))
    )
  )
  (nets
    (net (code "1") (name "/AIN5") (class "Default")
      (node (ref "ACS1") (pin "7") (pinfunction "VIOUT_7") (pintype "passive"))
      (node (ref "J2") (pin "54") (pinfunction "A0_54") (pintype "passive"))
    )
    (net (code "2") (name "/AIN6") (class "Default")
      (node (ref "ACS2") (pin "7") (pinfunction "VIOUT_7") (pintype "passive"))
      (node (ref "J2") (pin "55") (pinfunction "A1_55") (pintype "passive"))
    )
    (net (code "3") (name "/AIN7") (class "Default")
      (node (ref "ACS3") (pin "7") (pinfunction "VIOUT_7") (pintype "passive"))
      (node (ref "J2") (pin "56") (pinfunction "A2_56") (pintype "passive"))
    )
    (net (code "4") (name "/CHARGE_EN") (class "Default")
      (node (ref "J2") (pin "23") (pinfunction "DP23_23") (pintype "passive"))
      (node (ref "XL3") (pin "2") (pinfunction "EN_2") (pintype "passive"))
    )
    (net (code "5") (name "/CS1") (class "Default")
      (node (ref "J2") (pin "40") (pinfunction "DP40_40") (pintype "passive"))
      (node (ref "SD1") (pin "4") (pinfunction "CS/M2_4") (pintype "passive"))
    )
    (net (code "6") (name "/CS2") (class "Default")
      (node (ref "J2") (pin "53") (pinfunction "DP53/SPI_SS_53") (pintype "passive"))
      (node (ref "SD2") (pin "4") (pinfunction "CS/M2_4") (pintype "passive"))
    )
    (net (code "7") (name "/CS3") (class "Default")
      (node (ref "J2") (pin "34") (pinfunction "DP34_34") (pintype "passive"))
      (node (ref "SD3") (pin "4") (pinfunction "CS/M2_4") (pintype "passive"))
    )
    (net (code "8") (name "/CS4") (class "Default")
      (node (ref "J2") (pin "24") (pinfunction "DP24_24") (pintype "passive"))
      (node (ref "SD4") (pin "4") (pinfunction "CS/M2_4") (pintype "passive"))
    )
    (net (code "9") (name "/DIR1") (class "Default")
      (node (ref "J2") (pin "44") (pinfunction "DP44/PWM_44") (pintype "passive"))
      (node (ref "R8") (pin "2") (pinfunction "2_2") (pintype "passive"))
      (node (ref "SD1") (pin "8") (pinfunction "DIR_8") (pintype "passive"))
    )
    (net (code "10") (name "/DIR2") (class "Default")
      (node (ref "J2") (pin "48") (pinfunction "DP48_48") (pintype "passive"))
      (node (ref "R9") (pin "2") (pinfunction "2_2") (pintype "passive"))
      (node (ref "SD2") (pin "8") (pinfunction "DIR_8") (pintype "passive"))
    )
    (net (code "11") (name "/DIR3") (class "Default")
      (node (ref "J2") (pin "30") (pinfunction "DP30_30") (pintype "passive"))
      (node (ref "R13") (pin "2") (pinfunction "2_2") (pintype "passive"))
      (node (ref "SD3") (pin "8") (pinfunction "DIR_8") (pintype "passive"))
    )
    (net (code "12") (name "/DIR4") (class "Default")
      (node (ref "J2") (pin "28") (pinfunction "DP28_28") (pintype "passive"))
      (node (ref "R14") (pin "2") (pinfunction "2_2") (pintype "passive"))
      (node (ref "SD4") (pin "8") (pinfunction "DIR_8") (pintype "passive"))
    )
    (net (code "13") (name "/EN1") (class "Default")
      (node (ref "J2") (pin "38") (pinfunction "DP38_38") (pintype "passive"))
      (node (ref "SD1") (pin "1") (pinfunction "EN_1") (pintype "passive"))
    )
    (net (code "14") (name "/EN2") (class "Default")
      (node (ref "J2") (pin "49") (pinfunction "DP49_49") (pintype "passive"))
      (node (ref "SD2") (pin "1") (pinfunction "EN_1") (pintype "passive"))
    )
    (net (code "15") (name "/EN3") (class "Default")
      (node (ref "J2") (pin "36") (pinfunction "DP36_36") (pintype "passive"))
      (node (ref "SD3") (pin "1") (pinfunction "EN_1") (pintype "passive"))
    )
    (net (code "16") (name "/EN4") (class "Default")
      (node (ref "J2") (pin "22") (pinfunction "DP22_22") (pintype "passive"))
      (node (ref "SD4") (pin "1") (pinfunction "EN_1") (pintype "passive"))
    )
    (net (code "17") (name "/MISO") (class "Default")
      (node (ref "J2") (pin "50") (pinfunction "DP50/SPI_MISO_50") (pintype "passive"))
      (node (ref "R10") (pin "1") (pinfunction "1_1") (pintype "passive"))
      (node (ref "R11") (pin "2") (pinfunction "2_2") (pintype "passive"))
      (node (ref "R12") (pin "2") (pinfunction "2_2") (pintype "passive"))
      (node (ref "R15") (pin "2") (pinfunction "2_2") (pintype "passive"))
      (node (ref "R16") (pin "2") (pinfunction "2_2") (pintype "passive"))
      (node (ref "SD1") (pin "5") (pinfunction "SDO/RESET_5") (pintype "passive"))
      (node (ref "SD2") (pin "5") (pinfunction "SDO/RESET_5") (pintype "passive"))
      (node (ref "SD3") (pin "5") (pinfunction "SDO/RESET_5") (pintype "passive"))
      (node (ref "SD4") (pin "5") (pinfunction "SDO/RESET_5") (pintype "passive"))
    )
    (net (code "18") (name "/MOSI") (class "Default")
      (node (ref "J2") (pin "51") (pinfunction "DP51/SPI_MOSI_51") (pintype "passive"))
      (node (ref "SD1") (pin "2") (pinfunction "SDI/M0_2") (pintype "passive"))
      (node (ref "SD2") (pin "2") (pinfunction "SDI/M0_2") (pintype "passive"))
      (node (ref "SD3") (pin "2") (pinfunction "SDI/M0_2") (pintype "passive"))
      (node (ref "SD4") (pin "2") (pinfunction "SDI/M0_2") (pintype "passive"))
    )
    (net (code "19") (name "/SCK") (class "Default")
      (node (ref "J2") (pin "52") (pinfunction "DP52/SPI_SCK_52") (pintype "passive"))
      (node (ref "SD1") (pin "3") (pinfunction "SCK/M1_3") (pintype "passive"))
      (node (ref "SD2") (pin "3") (pinfunction "SCK/M1_3") (pintype "passive"))
      (node (ref "SD3") (pin "3") (pinfunction "SCK/M1_3") (pintype "passive"))
      (node (ref "SD4") (pin "3") (pinfunction "SCK/M1_3") (pintype "passive"))
    )
    (net (code "20") (name "/STP1") (class "Default")
      (node (ref "J2") (pin "5") (pinfunction "PWM/OC3A_5") (pintype "passive"))
      (node (ref "SD1") (pin "7") (pinfunction "STP_7") (pintype "passive"))
    )
    (net (code "21") (name "/STP2") (class "Default")
      (node (ref "J2") (pin "46") (pinfunction "DP46/PWM/OC5A_46") (pintype "passive"))
      (node (ref "SD2") (pin "7") (pinfunction "STP_7") (pintype "passive"))
    )
    (net (code "22") (name "/STP3") (class "Default")
      (node (ref "J2") (pin "11") (pinfunction "PWM/OC1A_11") (pintype "passive"))
      (node (ref "SD3") (pin "7") (pinfunction "STP_7") (pintype "passive"))
    )
    (net (code "23") (name "/STP4") (class "Default")
      (node (ref "J2") (pin "6") (pinfunction "PWM/OC4A_6") (pintype "passive"))
      (node (ref "SD4") (pin "7") (pinfunction "STP_7") (pintype "passive"))
    )
    (net (code "24") (name "5V") (class "Default")
      (node (ref "FB1") (pin "2") (pinfunction "2_2") (pintype "passive"))
      (node (ref "J1") (pin "3") (pinfunction "3_3") (pintype "passive"))
      (node (ref "J2") (pin "5V1") (pinfunction "5V_5V1") (pintype "passive"))
      (node (ref "J2") (pin "5V2") (pinfunction "5V_5V2") (pintype "passive"))
      (node (ref "R10") (pin "2") (pinfunction "2_2") (pintype "passive"))
      (node (ref "SD1") (pin "10") (pinfunction "VCC_10") (pintype "passive"))
      (node (ref "SD2") (pin "10") (pinfunction "VCC_10") (pintype "passive"))
      (node (ref "SD3") (pin "10") (pinfunction "VCC_10") (pintype "passive"))
      (node (ref "SD4") (pin "10") (pinfunction "VCC_10") (pintype "passive"))
    )
    (net (code "25") (name "5V_BUCK_OUT") (class "Default")
      (node (ref "ACS1") (pin "1") (pinfunction "IP+_1") (pintype "passive"))
      (node (ref "ACS1") (pin "2") (pinfunction "IP+_2") (pintype "passive"))
      (node (ref "C17") (pin "1") (pinfunction "1_1") (pintype "passive"))
      (node (ref "C19") (pin "2") (pinfunction "2_2") (pintype "passive"))
      (node (ref "C20") (pin "2") (pinfunction "2_2") (pintype "passive"))
      (node (ref "C21") (pin "2") (pinfunction "2_2") (pintype "passive"))
      (node (ref "C39") (pin "2") (pinfunction "2_2") (pintype "passive"))
      (node (ref "L2") (pin "2") (pinfunction "2_2") (pintype "passive"))
      (node (ref "R21") (pin "2") (pinfunction "2_2") (pintype "passive"))
    )
    (net (code "26") (name "5V_CHARGE") (class "Default")
      (node (ref "ACS3") (pin "3") (pinfunction "IP-_3") (pintype "passive"))
      (node (ref "ACS3") (pin "4") (pinfunction "IP-_4") (pintype "passive"))
      (node (ref "C29") (pin "1") (pinfunction "1_1") (pintype "passive"))
      (node (ref "C36") (pin "2") (pinfunction "2_2") (pintype "passive"))
      (node (ref "C37") (pin "2") (pinfunction "2_2") (pintype "passive"))
      (node (ref "C38") (pin "2") (pinfunction "2_2") (pintype "passive"))
      (node (ref "L1") (pin "2") (pinfunction "2_2") (pintype "passive"))
      (node (ref "XL3") (pin "4") (pinfunction "VIN_4") (pintype "passive"))
    )
    (net (code "27") (name "5V_CHARGING_IN") (class "Default")
      (node (ref "ACS3") (pin "1") (pinfunction "IP+_1") (pintype "passive"))
      (node (ref "ACS3") (pin "2") (pinfunction "IP+_2") (pintype "passive"))
      (node (ref "OT5") (pin "1") (pinfunction "1_1") (pintype "passive"))
      (node (ref "R18") (pin "2") (pinfunction "2_2") (pintype "passive"))
    )
    (net (code "28") (name "5V_OUT") (class "Default")
      (node (ref "ACS1") (pin "3") (pinfunction "IP-_3") (pintype "passive"))
      (node (ref "ACS1") (pin "4") (pinfunction "IP-_4") (pintype "passive"))
      (node (ref "OT1") (pin "1") (pinfunction "1_1") (pintype "passive"))
    )
    (net (code "29") (name "12V_BUCK_OUT") (class "Default")
      (node (ref "ACS2") (pin "1") (pinfunction "IP+_1") (pintype "passive"))
      (node (ref "ACS2") (pin "2") (pinfunction "IP+_2") (pintype "passive"))
      (node (ref "C18") (pin "1") (pinfunction "1_1") (pintype "passive"))
      (node (ref "C24") (pin "2") (pinfunction "2_2") (pintype "passive"))
      (node (ref "C25") (pin "2") (pinfunction "2_2") (pintype "passive"))
      (node (ref "C26") (pin "2") (pinfunction "2_2") (pintype "passive"))
      (node (ref "C40") (pin "2") (pinfunction "2_2") (pintype "passive"))
      (node (ref "L3") (pin "2") (pinfunction "2_2") (pintype "passive"))
      (node (ref "R22") (pin "2") (pinfunction "2_2") (pintype "passive"))
    )
    (net (code "30") (name "12V_OUT") (class "Default")
      (node (ref "ACS2") (pin "3") (pinfunction "IP-_3") (pintype "passive"))
      (node (ref "ACS2") (pin "4") (pinfunction "IP-_4") (pintype "passive"))
      (node (ref "OT3") (pin "1") (pinfunction "1_1") (pintype "passive"))
    )
    (net (code "31") (name "FILTERED_5V") (class "Default")
      (node (ref "ACS1") (pin "8") (pinfunction "VCC_8") (pintype "passive"))
      (node (ref "ACS2") (pin "8") (pinfunction "VCC_8") (pintype "passive"))
      (node (ref "ACS3") (pin "8") (pinfunction "VCC_8") (pintype "passive"))
      (node (ref "C2") (pin "2") (pinfunction "2_2") (pintype "passive"))
      (node (ref "C3") (pin "2") (pinfunction "2_2") (pintype "passive"))
      (node (ref "C4") (pin "2") (pinfunction "2_2") (pintype "passive"))
      (node (ref "FB1") (pin "1") (pinfunction "1_1") (pintype "passive"))
    )
    (net (code "32") (name "GND") (class "Default")
      (node (ref "ACS1") (pin "5") (pinfunction "GND_5") (pintype "passive"))
      (node (ref "ACS1") (pin "6") (pinfunction "BW_SEL_6") (pintype "passive"))
      (node (ref "ACS2") (pin "5") (pinfunction "GND_5") (pintype "passive"))
      (node (ref "ACS2") (pin "6") (pinfunction "BW_SEL_6") (pintype "passive"))
      (node (ref "ACS3") (pin "5") (pinfunction "GND_5") (pintype "passive"))
      (node (ref "ACS3") (pin "6") (pinfunction "BW_SEL_6") (pintype "passive"))
      (node (ref "BT2") (pin "1") (pinfunction "1_1") (pintype "passive"))
      (node (ref "C1") (pin "1") (pinfunction "1_1") (pintype "passive"))
      (node (ref "C12") (pin "1") (pinfunction "1_1") (pintype "passive"))
      (node (ref "C13") (pin "1") (pinfunction "1_1") (pintype "passive"))
      (node (ref "C14") (pin "1") (pinfunction "1_1") (pintype "passive"))
      (node (ref "C17") (pin "2") (pinfunction "2_2") (pintype "passive"))
      (node (ref "C18") (pin "2") (pinfunction "2_2") (pintype "passive"))
      (node (ref "C19") (pin "1") (pinfunction "1_1") (pintype "passive"))
      (node (ref "C2") (pin "1") (pinfunction "1_1") (pintype "passive"))
      (node (ref "C20") (pin "1") (pinfunction "1_1") (pintype "passive"))
      (node (ref "C21") (pin "1") (pinfunction "1_1") (pintype "passive"))
      (node (ref "C24") (pin "1") (pinfunction "1_1") (pintype "passive"))
      (node (ref "C25") (pin "1") (pinfunction "1_1") (pintype "passive"))
      (node (ref "C26") (pin "1") (pinfunction "1_1") (pintype "passive"))
      (node (ref "C27") (pin "2") (pinfunction "2_2") (pintype "passive"))
      (node (ref "C28") (pin "2") (pinfunction "2_2") (pintype "passive"))
      (node (ref "C29") (pin "2") (pinfunction "2_2") (pintype "passive"))
      (node (ref "C3") (pin "1") (pinfunction "1_1") (pintype "passive"))
      (node (ref "C30") (pin "1") (pinfunction "1_1") (pintype "passive"))
      (node (ref "C31") (pin "1") (pinfunction "1_1") (pintype "passive"))
      (node (ref "C32") (pin "1") (pinfunction "1_1") (pintype "passive"))
      (node (ref "C33") (pin "1") (pinfunction "1_1") (pintype "passive"))
      (node (ref "C34") (pin "1") (pinfunction "1_1") (pintype "passive"))
      (node (ref "C36") (pin "1") (pinfunction "1_1") (pintype "passive"))
      (node (ref "C37") (pin "1") (pinfunction "1_1") (pintype "passive"))
      (node (ref "C38") (pin "1") (pinfunction "1_1") (pintype "passive"))
      (node (ref "C4") (pin "1") (pinfunction "1_1") (pintype "passive"))
      (node (ref "C5") (pin "1") (pinfunction "1_1") (pintype "passive"))
      (node (ref "C6") (pin "1") (pinfunction "1_1") (pintype "passive"))
      (node (ref "C7") (pin "1") (pinfunction "1_1") (pintype "passive"))
      (node (ref "D1") (pin "-") (pinfunction "-_-") (pintype "passive"))
      (node (ref "D2") (pin "-") (pinfunction "-_-") (pintype "passive"))
      (node (ref "D3") (pin "-") (pinfunction "-_-") (pintype "passive"))
      (node (ref "D4") (pin "-") (pinfunction "-_-") (pintype "passive"))
      (node (ref "D5") (pin "-") (pinfunction "-_-") (pintype "passive"))
      (node (ref "D6") (pin "-") (pinfunction "-_-") (pintype "passive"))
      (node (ref "D8") (pin "1") (pinfunction "1_1") (pintype "passive"))
      (node (ref "D9") (pin "1") (pinfunction "1_1") (pintype "passive"))
      (node (ref "J1") (pin "1") (pinfunction "1_1") (pintype "passive"))
      (node (ref "J1") (pin "2") (pinfunction "2_2") (pintype "passive"))
      (node (ref "J2") (pin "GND1") (pinfunction "GND_GND1") (pintype "passive"))
      (node (ref "J2") (pin "GND2") (pinfunction "GND_GND2") (pintype "passive"))
      (node (ref "OT2") (pin "1") (pinfunction "1_1") (pintype "passive"))
      (node (ref "OT4") (pin "1") (pinfunction "1_1") (pintype "passive"))
      (node (ref "OT6") (pin "1") (pinfunction "1_1") (pintype "passive"))
      (node (ref "R1") (pin "2") (pinfunction "2_2") (pintype "passive"))
      (node (ref "R20") (pin "1") (pinfunction "1_1") (pintype "passive"))
      (node (ref "R23") (pin "1") (pinfunction "1_1") (pintype "passive"))
      (node (ref "R24") (pin "1") (pinfunction "1_1") (pintype "passive"))
      (node (ref "R3") (pin "2") (pinfunction "2_2") (pintype "passive"))
      (node (ref "R5") (pin "2") (pinfunction "2_2") (pintype "passive"))
      (node (ref "SD1") (pin "15") (pinfunction "GND_15") (pintype "passive"))
      (node (ref "SD1") (pin "9") (pinfunction "GND_9") (pintype "passive"))
      (node (ref "SD2") (pin "15") (pinfunction "GND_15") (pintype "passive"))
      (node (ref "SD2") (pin "9") (pinfunction "GND_9") (pintype "passive"))
      (node (ref "SD3") (pin "15") (pinfunction "GND_15") (pintype "passive"))
      (node (ref "SD3") (pin "9") (pinfunction "GND_9") (pintype "passive"))
      (node (ref "SD4") (pin "15") (pinfunction "GND_15") (pintype "passive"))
      (node (ref "SD4") (pin "9") (pinfunction "GND_9") (pintype "passive"))
      (node (ref "XL1") (pin "1") (pinfunction "GND_1") (pintype "passive"))
      (node (ref "XL2") (pin "1") (pinfunction "GND_1") (pintype "passive"))
      (node (ref "XL3") (pin "1") (pinfunction "GND_1") (pintype "passive"))
    )
    (net (code "33") (name "Net-(D1-Pad+)") (class "Default")
      (node (ref "D1") (pin "+") (pinfunction "+_+") (pintype "passive"))
      (node (ref "R8") (pin "1") (pinfunction "1_1") (pintype "passive"))
    )
    (net (code "34") (name "Net-(D2-Pad+)") (class "Default")
      (node (ref "D2") (pin "+") (pinfunction "+_+") (pintype "passive"))
      (node (ref "R9") (pin "1") (pinfunction "1_1") (pintype "passive"))
    )
    (net (code "35") (name "Net-(D3-Pad+)") (class "Default")
      (node (ref "D3") (pin "+") (pinfunction "+_+") (pintype "passive"))
      (node (ref "R13") (pin "1") (pinfunction "1_1") (pintype "passive"))
    )
    (net (code "36") (name "Net-(D4-Pad+)") (class "Default")
      (node (ref "D4") (pin "+") (pinfunction "+_+") (pintype "passive"))
      (node (ref "R14") (pin "1") (pinfunction "1_1") (pintype "passive"))
    )
    (net (code "37") (name "Net-(D5-Pad+)") (class "Default")
      (node (ref "D5") (pin "+") (pinfunction "+_+") (pintype "passive"))
      (node (ref "R17") (pin "1") (pinfunction "1_1") (pintype "passive"))
    )
    (net (code "38") (name "Net-(D6-Pad+)") (class "Default")
      (node (ref "D6") (pin "+") (pinfunction "+_+") (pintype "passive"))
      (node (ref "R18") (pin "1") (pinfunction "1_1") (pintype "passive"))
    )
    (net (code "39") (name "Net-(J1-Pad5)") (class "Default")
      (node (ref "J1") (pin "5") (pinfunction "5_5") (pintype "passive"))
      (node (ref "R7") (pin "1") (pinfunction "1_1") (pintype "passive"))
    )
    (net (code "40") (name "Net-(J1-Pad6)") (class "Default")
      (node (ref "J1") (pin "6") (pinfunction "6_6") (pintype "passive"))
      (node (ref "R6") (pin "1") (pinfunction "1_1") (pintype "passive"))
    )
    (net (code "41") (name "Net-(J1-Pad7)") (class "Default")
      (node (ref "J1") (pin "7") (pinfunction "7_7") (pintype "passive"))
      (node (ref "R4") (pin "1") (pinfunction "1_1") (pintype "passive"))
    )
    (net (code "42") (name "Net-(J1-Pad8)") (class "Default")
      (node (ref "J1") (pin "8") (pinfunction "8_8") (pintype "passive"))
      (node (ref "R2") (pin "1") (pinfunction "1_1") (pintype "passive"))
    )
    (net (code "43") (name "Net-(J2-A3)") (class "Default")
      (node (ref "C1") (pin "2") (pinfunction "2_2") (pintype "passive"))
      (node (ref "J2") (pin "57") (pinfunction "A3_57") (pintype "passive"))
      (node (ref "R1") (pin "1") (pinfunction "1_1") (pintype "passive"))
      (node (ref "R2") (pin "2") (pinfunction "2_2") (pintype "passive"))
    )
    (net (code "44") (name "Net-(J2-A4)") (class "Default")
      (node (ref "C5") (pin "2") (pinfunction "2_2") (pintype "passive"))
      (node (ref "J2") (pin "58") (pinfunction "A4_58") (pintype "passive"))
      (node (ref "R3") (pin "1") (pinfunction "1_1") (pintype "passive"))
      (node (ref "R4") (pin "2") (pinfunction "2_2") (pintype "passive"))
    )
    (net (code "45") (name "Net-(J2-A5)") (class "Default")
      (node (ref "C6") (pin "2") (pinfunction "2_2") (pintype "passive"))
      (node (ref "J2") (pin "59") (pinfunction "A5_59") (pintype "passive"))
      (node (ref "R5") (pin "1") (pinfunction "1_1") (pintype "passive"))
      (node (ref "R6") (pin "2") (pinfunction "2_2") (pintype "passive"))
    )
    (net (code "46") (name "Net-(J2-A6)") (class "Default")
      (node (ref "C7") (pin "2") (pinfunction "2_2") (pintype "passive"))
      (node (ref "J2") (pin "60") (pinfunction "A6_60") (pintype "passive"))
      (node (ref "R7") (pin "2") (pinfunction "2_2") (pintype "passive"))
    )
    (net (code "47") (name "Net-(J2-A7)") (class "Default")
      (node (ref "J1") (pin "4") (pinfunction "4_4") (pintype "passive"))
      (node (ref "J2") (pin "61") (pinfunction "A7_61") (pintype "passive"))
    )
    (net (code "48") (name "Net-(J3-1A)") (class "Default")
      (node (ref "J3") (pin "3") (pinfunction "1A_3") (pintype "passive"))
      (node (ref "SD1") (pin "12") (pinfunction "1A_12") (pintype "passive"))
    )
    (net (code "49") (name "Net-(J3-1B)") (class "Default")
      (node (ref "J3") (pin "2") (pinfunction "1B_2") (pintype "passive"))
      (node (ref "SD1") (pin "13") (pinfunction "1B_13") (pintype "passive"))
    )
    (net (code "50") (name "Net-(J3-2A)") (class "Default")
      (node (ref "J3") (pin "4") (pinfunction "2A_4") (pintype "passive"))
      (node (ref "SD1") (pin "11") (pinfunction "2A_11") (pintype "passive"))
    )
    (net (code "51") (name "Net-(J3-2B)") (class "Default")
      (node (ref "J3") (pin "1") (pinfunction "2B_1") (pintype "passive"))
      (node (ref "SD1") (pin "14") (pinfunction "2B_14") (pintype "passive"))
    )
    (net (code "52") (name "Net-(J4-1A)") (class "Default")
      (node (ref "J4") (pin "3") (pinfunction "1A_3") (pintype "passive"))
      (node (ref "SD3") (pin "12") (pinfunction "1A_12") (pintype "passive"))
    )
    (net (code "53") (name "Net-(J4-1B)") (class "Default")
      (node (ref "J4") (pin "2") (pinfunction "1B_2") (pintype "passive"))
      (node (ref "SD3") (pin "13") (pinfunction "1B_13") (pintype "passive"))
    )
    (net (code "54") (name "Net-(J4-2A)") (class "Default")
      (node (ref "J4") (pin "4") (pinfunction "2A_4") (pintype "passive"))
      (node (ref "SD3") (pin "11") (pinfunction "2A_11") (pintype "passive"))
    )
    (net (code "55") (name "Net-(J4-2B)") (class "Default")
      (node (ref "J4") (pin "1") (pinfunction "2B_1") (pintype "passive"))
      (node (ref "SD3") (pin "14") (pinfunction "2B_14") (pintype "passive"))
    )
    (net (code "56") (name "Net-(J5-1A)") (class "Default")
      (node (ref "J5") (pin "3") (pinfunction "1A_3") (pintype "passive"))
      (node (ref "SD2") (pin "12") (pinfunction "1A_12") (pintype "passive"))
    )
    (net (code "57") (name "Net-(J5-1B)") (class "Default")
      (node (ref "J5") (pin "2") (pinfunction "1B_2") (pintype "passive"))
      (node (ref "SD2") (pin "13") (pinfunction "1B_13") (pintype "passive"))
    )
    (net (code "58") (name "Net-(J5-2A)") (class "Default")
      (node (ref "J5") (pin "4") (pinfunction "2A_4") (pintype "passive"))
      (node (ref "SD2") (pin "11") (pinfunction "2A_11") (pintype "passive"))
    )
    (net (code "59") (name "Net-(J5-2B)") (class "Default")
      (node (ref "J5") (pin "1") (pinfunction "2B_1") (pintype "passive"))
      (node (ref "SD2") (pin "14") (pinfunction "2B_14") (pintype "passive"))
    )
    (net (code "60") (name "Net-(J6-1A)") (class "Default")
      (node (ref "J6") (pin "3") (pinfunction "1A_3") (pintype "passive"))
      (node (ref "SD4") (pin "12") (pinfunction "1A_12") (pintype "passive"))
    )
    (net (code "61") (name "Net-(J6-1B)") (class "Default")
      (node (ref "J6") (pin "2") (pinfunction "1B_2") (pintype "passive"))
      (node (ref "SD4") (pin "13") (pinfunction "1B_13") (pintype "passive"))
    )
    (net (code "62") (name "Net-(J6-2A)") (class "Default")
      (node (ref "J6") (pin "4") (pinfunction "2A_4") (pintype "passive"))
      (node (ref "SD4") (pin "11") (pinfunction "2A_11") (pintype "passive"))
    )
    (net (code "63") (name "Net-(J6-2B)") (class "Default")
      (node (ref "J6") (pin "1") (pinfunction "2B_1") (pintype "passive"))
      (node (ref "SD4") (pin "14") (pinfunction "2B_14") (pintype "passive"))
    )
    (net (code "64") (name "Net-(SD1-NC{slash}SLEEP)") (class "Default")
      (node (ref "R11") (pin "1") (pinfunction "1_1") (pintype "passive"))
      (node (ref "SD1") (pin "6") (pinfunction "NC/SLEEP_6") (pintype "passive"))
    )
    (net (code "65") (name "Net-(SD2-NC{slash}SLEEP)") (class "Default")
      (node (ref "R15") (pin "1") (pinfunction "1_1") (pintype "passive"))
      (node (ref "SD2") (pin "6") (pinfunction "NC/SLEEP_6") (pintype "passive"))
    )
    (net (code "66") (name "Net-(SD3-NC{slash}SLEEP)") (class "Default")
      (node (ref "R12") (pin "1") (pinfunction "1_1") (pintype "passive"))
      (node (ref "SD3") (pin "6") (pinfunction "NC/SLEEP_6") (pintype "passive"))
    )
    (net (code "67") (name "Net-(SD4-NC{slash}SLEEP)") (class "Default")
      (node (ref "R16") (pin "1") (pinfunction "1_1") (pintype "passive"))
      (node (ref "SD4") (pin "6") (pinfunction "NC/SLEEP_6") (pintype "passive"))
    )
    (net (code "68") (name "Net-(XL1-FB)") (class "Default")
      (node (ref "C39") (pin "1") (pinfunction "1_1") (pintype "passive"))
      (node (ref "R21") (pin "1") (pinfunction "1_1") (pintype "passive"))
      (node (ref "R23") (pin "2") (pinfunction "2_2") (pintype "passive"))
      (node (ref "XL1") (pin "2") (pinfunction "FB_2") (pintype "passive"))
    )
    (net (code "69") (name "Net-(XL1-SW)") (class "Default")
      (node (ref "D8") (pin "2") (pinfunction "2_2") (pintype "passive"))
      (node (ref "L2") (pin "1") (pinfunction "1_1") (pintype "passive"))
      (node (ref "XL1") (pin "3") (pinfunction "SW_3") (pintype "passive"))
    )
    (net (code "70") (name "Net-(XL1-VC)") (class "Default")
      (node (ref "C15") (pin "1") (pinfunction "1_1") (pintype "passive"))
      (node (ref "XL1") (pin "4") (pinfunction "VC_4") (pintype "passive"))
    )
    (net (code "71") (name "Net-(XL2-FB)") (class "Default")
      (node (ref "C40") (pin "1") (pinfunction "1_1") (pintype "passive"))
      (node (ref "R22") (pin "1") (pinfunction "1_1") (pintype "passive"))
      (node (ref "R24") (pin "2") (pinfunction "2_2") (pintype "passive"))
      (node (ref "XL2") (pin "2") (pinfunction "FB_2") (pintype "passive"))
    )
    (net (code "72") (name "Net-(XL2-SW)") (class "Default")
      (node (ref "D9") (pin "2") (pinfunction "2_2") (pintype "passive"))
      (node (ref "L3") (pin "1") (pinfunction "1_1") (pintype "passive"))
      (node (ref "XL2") (pin "3") (pinfunction "SW_3") (pintype "passive"))
    )
    (net (code "73") (name "Net-(XL2-VC)") (class "Default")
      (node (ref "C16") (pin "1") (pinfunction "1_1") (pintype "passive"))
      (node (ref "XL2") (pin "4") (pinfunction "VC_4") (pintype "passive"))
    )
    (net (code "74") (name "Net-(XL3-FB)") (class "Default")
      (node (ref "R19") (pin "1") (pinfunction "1_1") (pintype "passive"))
      (node (ref "R20") (pin "2") (pinfunction "2_2") (pintype "passive"))
      (node (ref "XL3") (pin "5") (pinfunction "FB_5") (pintype "passive"))
    )
    (net (code "75") (name "Net-(XL3-SW)") (class "Default")
      (node (ref "D7") (pin "1") (pinfunction "1_1") (pintype "passive"))
      (node (ref "L1") (pin "1") (pinfunction "1_1") (pintype "passive"))
      (node (ref "XL3") (pin "3") (pinfunction "SW_3") (pintype "passive"))
    )
    (net (code "76") (name "VBAT") (class "Default")
      (node (ref "BT1") (pin "1") (pinfunction "1_1") (pintype "passive"))
      (node (ref "C12") (pin "2") (pinfunction "2_2") (pintype "passive"))
      (node (ref "C13") (pin "2") (pinfunction "2_2") (pintype "passive"))
      (node (ref "C14") (pin "2") (pinfunction "2_2") (pintype "passive"))
      (node (ref "C15") (pin "2") (pinfunction "2_2") (pintype "passive"))
      (node (ref "C16") (pin "2") (pinfunction "2_2") (pintype "passive"))
      (node (ref "C27") (pin "1") (pinfunction "1_1") (pintype "passive"))
      (node (ref "C28") (pin "1") (pinfunction "1_1") (pintype "passive"))
      (node (ref "C30") (pin "2") (pinfunction "2_2") (pintype "passive"))
      (node (ref "C31") (pin "2") (pinfunction "2_2") (pintype "passive"))
      (node (ref "C32") (pin "2") (pinfunction "2_2") (pintype "passive"))
      (node (ref "C33") (pin "2") (pinfunction "2_2") (pintype "passive"))
      (node (ref "C34") (pin "2") (pinfunction "2_2") (pintype "passive"))
      (node (ref "D7") (pin "2") (pinfunction "2_2") (pintype "passive"))
      (node (ref "R17") (pin "2") (pinfunction "2_2") (pintype "passive"))
      (node (ref "R19") (pin "2") (pinfunction "2_2") (pintype "passive"))
      (node (ref "SD1") (pin "16") (pinfunction "VM_16") (pintype "passive"))
      (node (ref "SD2") (pin "16") (pinfunction "VM_16") (pintype "passive"))
      (node (ref "SD3") (pin "16") (pinfunction "VM_16") (pintype "passive"))
      (node (ref "SD4") (pin "16") (pinfunction "VM_16") (pintype "passive"))
      (node (ref "XL1") (pin "5") (pinfunction "VIN_5") (pintype "passive"))
      (node (ref "XL2") (pin "5") (pinfunction "VIN_5") (pintype "passive"))
    )
    (net (code "77") (name "unconnected-(J2-DP25-Pad25)") (class "Default")
      (node (ref "J2") (pin "25") (pinfunction "DP25_25") (pintype "passive"))
    )
    (net (code "78") (name "unconnected-(J2-DP26-Pad26)") (class "Default")
      (node (ref "J2") (pin "26") (pinfunction "DP26_26") (pintype "passive"))
    )
    (net (code "79") (name "unconnected-(J2-DP27-Pad27)") (class "Default")
      (node (ref "J2") (pin "27") (pinfunction "DP27_27") (pintype "passive"))
    )
    (net (code "80") (name "unconnected-(J2-DP29-Pad29)") (class "Default")
      (node (ref "J2") (pin "29") (pinfunction "DP29_29") (pintype "passive"))
    )
    (net (code "81") (name "unconnected-(J2-DP31-Pad31)") (class "Default")
      (node (ref "J2") (pin "31") (pinfunction "DP31_31") (pintype "passive"))
    )
    (net (code "82") (name "unconnected-(J2-DP32-Pad32)") (class "Default")
      (node (ref "J2") (pin "32") (pinfunction "DP32_32") (pintype "passive"))
    )
    (net (code "83") (name "unconnected-(J2-DP33-Pad33)") (class "Default")
      (node (ref "J2") (pin "33") (pinfunction "DP33_33") (pintype "passive"))
    )
    (net (code "84") (name "unconnected-(J2-DP35-Pad35)") (class "Default")
      (node (ref "J2") (pin "35") (pinfunction "DP35_35") (pintype "passive"))
    )
    (net (code "85") (name "unconnected-(J2-DP37-Pad37)") (class "Default")
      (node (ref "J2") (pin "37") (pinfunction "DP37_37") (pintype "passive"))
    )
    (net (code "86") (name "unconnected-(J2-DP39-Pad39)") (class "Default")
      (node (ref "J2") (pin "39") (pinfunction "DP39_39") (pintype "passive"))
    )
    (net (code "87") (name "unconnected-(J2-DP41-Pad41)") (class "Default")
      (node (ref "J2") (pin "41") (pinfunction "DP41_41") (pintype "passive"))
    )
    (net (code "88") (name "unconnected-(J2-DP42-Pad42)") (class "Default")
      (node (ref "J2") (pin "42") (pinfunction "DP42_42") (pintype "passive"))
    )
    (net (code "89") (name "unconnected-(J2-DP43-Pad43)") (class "Default")
      (node (ref "J2") (pin "43") (pinfunction "DP43_43") (pintype "passive"))
    )
    (net (code "90") (name "unconnected-(J2-DP45{slash}PWM-Pad45)") (class "Default")
      (node (ref "J2") (pin "45") (pinfunction "DP45/PWM_45") (pintype "passive"))
    )
    (net (code "91") (name "unconnected-(J2-DP47-Pad47)") (class "Default")
      (node (ref "J2") (pin "47") (pinfunction "DP47_47") (pintype "passive"))
    )
    (net (code "92") (name "unconnected-(J2-PWM{slash}OC0B-Pad4)") (class "Default")
      (node (ref "J2") (pin "4") (pinfunction "PWM/OC0B_4") (pintype "passive"))
    )
    (net (code "93") (name "unconnected-(J2-PWM{slash}OC2A-Pad10)") (class "Default")
      (node (ref "J2") (pin "10") (pinfunction "PWM/OC2A_10") (pintype "passive"))
    )
    (net (code "94") (name "unconnected-(J2-PWM{slash}OC2B-Pad9)") (class "Default")
      (node (ref "J2") (pin "9") (pinfunction "PWM/OC2B_9") (pintype "passive"))
    )
    (net (code "95") (name "unconnected-(J2-PWM{slash}OC4B-Pad7)") (class "Default")
      (node (ref "J2") (pin "7") (pinfunction "PWM/OC4B_7") (pintype "passive"))
    )
    (net (code "96") (name "unconnected-(J2-PWM{slash}OC4C-Pad8)") (class "Default")
      (node (ref "J2") (pin "8") (pinfunction "PWM/OC4C_8") (pintype "passive"))
    )
  )
)
